# raveGear301.net
KiCad netlist of a schematic drawn in EAGLE
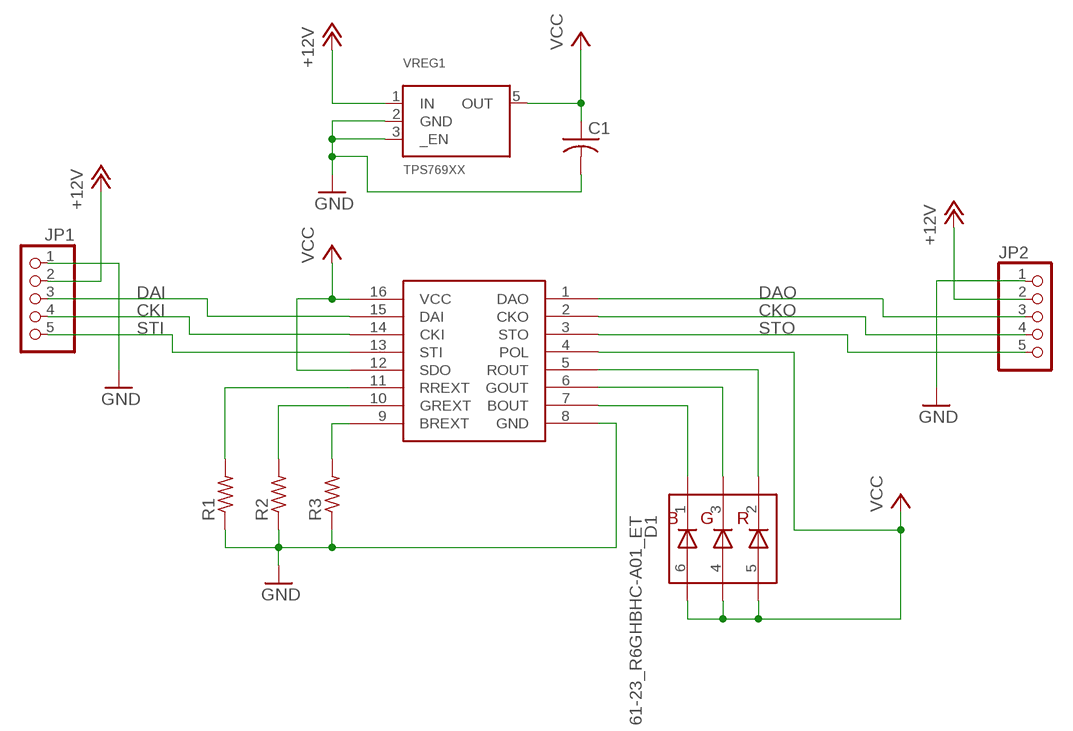
[diagram p0: schematic, sheet 1]

(export (version "E")
  (design (tool "Eeschema 10.0.6"))
  (components
    (comp (ref "C1")
      (value "C-USC0603")
      (footprint "eagle-import:C0603")
      (libsource (lib "eagle-import") (part "C-USC0603"))
    )
    (comp (ref "D1")
      (value "61-23_R6GHBHC-A01_ET")
      (footprint "eagle-import:LF-6")
      (libsource (lib "eagle-import") (part "61-23_R6GHBHC-A01_ET"))
    )
    (comp (ref "JP1")
      (value "PINHD-1X5")
      (footprint "eagle-import:1X05")
      (libsource (lib "eagle-import") (part "PINHD-1X5"))
    )
    (comp (ref "JP2")
      (value "PINHD-1X5")
      (footprint "eagle-import:1X05")
      (libsource (lib "eagle-import") (part "PINHD-1X5"))
    )
    (comp (ref "R1")
      (value "R-US_R0402")
      (footprint "eagle-import:R0402")
      (libsource (lib "eagle-import") (part "R-US_R0402"))
    )
    (comp (ref "R2")
      (value "R-US_R0402")
      (footprint "eagle-import:R0402")
      (libsource (lib "eagle-import") (part "R-US_R0402"))
    )
    (comp (ref "R3")
      (value "R-US_R0402")
      (footprint "eagle-import:R0402")
      (libsource (lib "eagle-import") (part "R-US_R0402"))
    )
    (comp (ref "U1")
      (value "DM412BEST")
      (footprint "eagle-import:SSOP16")
      (libsource (lib "eagle-import") (part "DM412BEST"))
    )
    (comp (ref "VREG1")
      (value "TPS769XX")
      (footprint "eagle-import:SOT23-5L")
      (libsource (lib "eagle-import") (part "TPS769XX"))
    )
  )
  (nets
    (net (code "1") (name "+12V") (class "Default")
      (node (ref "JP1") (pin "2") (pinfunction "2_2") (pintype "passive"))
      (node (ref "JP2") (pin "2") (pinfunction "2_2") (pintype "passive"))
      (node (ref "VREG1") (pin "1") (pinfunction "IN_1") (pintype "input"))
    )
    (net (code "2") (name "/CKI") (class "Default")
      (node (ref "JP1") (pin "4") (pinfunction "4_4") (pintype "passive"))
      (node (ref "U1") (pin "14") (pinfunction "CKI_14") (pintype "input"))
    )
    (net (code "3") (name "/CKO") (class "Default")
      (node (ref "JP2") (pin "4") (pinfunction "4_4") (pintype "passive"))
      (node (ref "U1") (pin "2") (pinfunction "CKO_2") (pintype "output"))
    )
    (net (code "4") (name "/DAI") (class "Default")
      (node (ref "JP1") (pin "3") (pinfunction "3_3") (pintype "passive"))
      (node (ref "U1") (pin "15") (pinfunction "DAI_15") (pintype "input"))
    )
    (net (code "5") (name "/DAO") (class "Default")
      (node (ref "JP2") (pin "3") (pinfunction "3_3") (pintype "passive"))
      (node (ref "U1") (pin "1") (pinfunction "DAO_1") (pintype "output"))
    )
    (net (code "6") (name "/STI") (class "Default")
      (node (ref "JP1") (pin "5") (pinfunction "5_5") (pintype "passive"))
      (node (ref "U1") (pin "13") (pinfunction "STI_13") (pintype "input"))
    )
    (net (code "7") (name "/STO") (class "Default")
      (node (ref "JP2") (pin "5") (pinfunction "5_5") (pintype "passive"))
      (node (ref "U1") (pin "3") (pinfunction "STO_3") (pintype "output"))
    )
    (net (code "8") (name "GND") (class "Default")
      (node (ref "C1") (pin "2") (pinfunction "2_2") (pintype "passive"))
      (node (ref "JP1") (pin "1") (pinfunction "1_1") (pintype "passive"))
      (node (ref "JP2") (pin "1") (pinfunction "1_1") (pintype "passive"))
      (node (ref "R1") (pin "1") (pinfunction "1_1") (pintype "passive"))
      (node (ref "R2") (pin "1") (pinfunction "1_1") (pintype "passive"))
      (node (ref "R3") (pin "1") (pinfunction "1_1") (pintype "passive"))
      (node (ref "U1") (pin "8") (pinfunction "GND_8") (pintype "power_in"))
      (node (ref "VREG1") (pin "2") (pinfunction "GND_2") (pintype "input"))
      (node (ref "VREG1") (pin "3") (pinfunction "_EN_3") (pintype "input"))
    )
    (net (code "9") (name "Net-(D1-CB)") (class "Default")
      (node (ref "D1") (pin "1") (pinfunction "CB_1") (pintype "passive"))
      (node (ref "U1") (pin "7") (pinfunction "BOUT_7") (pintype "bidirectional"))
    )
    (net (code "10") (name "Net-(D1-CG)") (class "Default")
      (node (ref "D1") (pin "3") (pinfunction "CG_3") (pintype "passive"))
      (node (ref "U1") (pin "6") (pinfunction "GOUT_6") (pintype "bidirectional"))
    )
    (net (code "11") (name "Net-(D1-CR)") (class "Default")
      (node (ref "D1") (pin "2") (pinfunction "CR_2") (pintype "passive"))
      (node (ref "U1") (pin "5") (pinfunction "ROUT_5") (pintype "bidirectional"))
    )
    (net (code "12") (name "Net-(U1-BREXT)") (class "Default")
      (node (ref "R3") (pin "2") (pinfunction "2_2") (pintype "passive"))
      (node (ref "U1") (pin "9") (pinfunction "BREXT_9") (pintype "bidirectional"))
    )
    (net (code "13") (name "Net-(U1-GREXT)") (class "Default")
      (node (ref "R2") (pin "2") (pinfunction "2_2") (pintype "passive"))
      (node (ref "U1") (pin "10") (pinfunction "GREXT_10") (pintype "bidirectional"))
    )
    (net (code "14") (name "Net-(U1-RREXT)") (class "Default")
      (node (ref "R1") (pin "2") (pinfunction "2_2") (pintype "passive"))
      (node (ref "U1") (pin "11") (pinfunction "RREXT_11") (pintype "bidirectional"))
    )
    (net (code "15") (name "VCC") (class "Default")
      (node (ref "C1") (pin "1") (pinfunction "1_1") (pintype "passive"))
      (node (ref "D1") (pin "4") (pinfunction "AG_4") (pintype "passive"))
      (node (ref "D1") (pin "5") (pinfunction "AR_5") (pintype "passive"))
      (node (ref "D1") (pin "6") (pinfunction "AB_6") (pintype "passive"))
      (node (ref "U1") (pin "12") (pinfunction "SDO_12") (pintype "bidirectional"))
      (node (ref "U1") (pin "16") (pinfunction "VCC_16") (pintype "power_in"))
      (node (ref "U1") (pin "4") (pinfunction "POL_4") (pintype "bidirectional"))
      (node (ref "VREG1") (pin "5") (pinfunction "OUT_5") (pintype "output"))
    )
  )
)
